# rk8-05.net
KiCad netlist of a schematic drawn in EAGLE
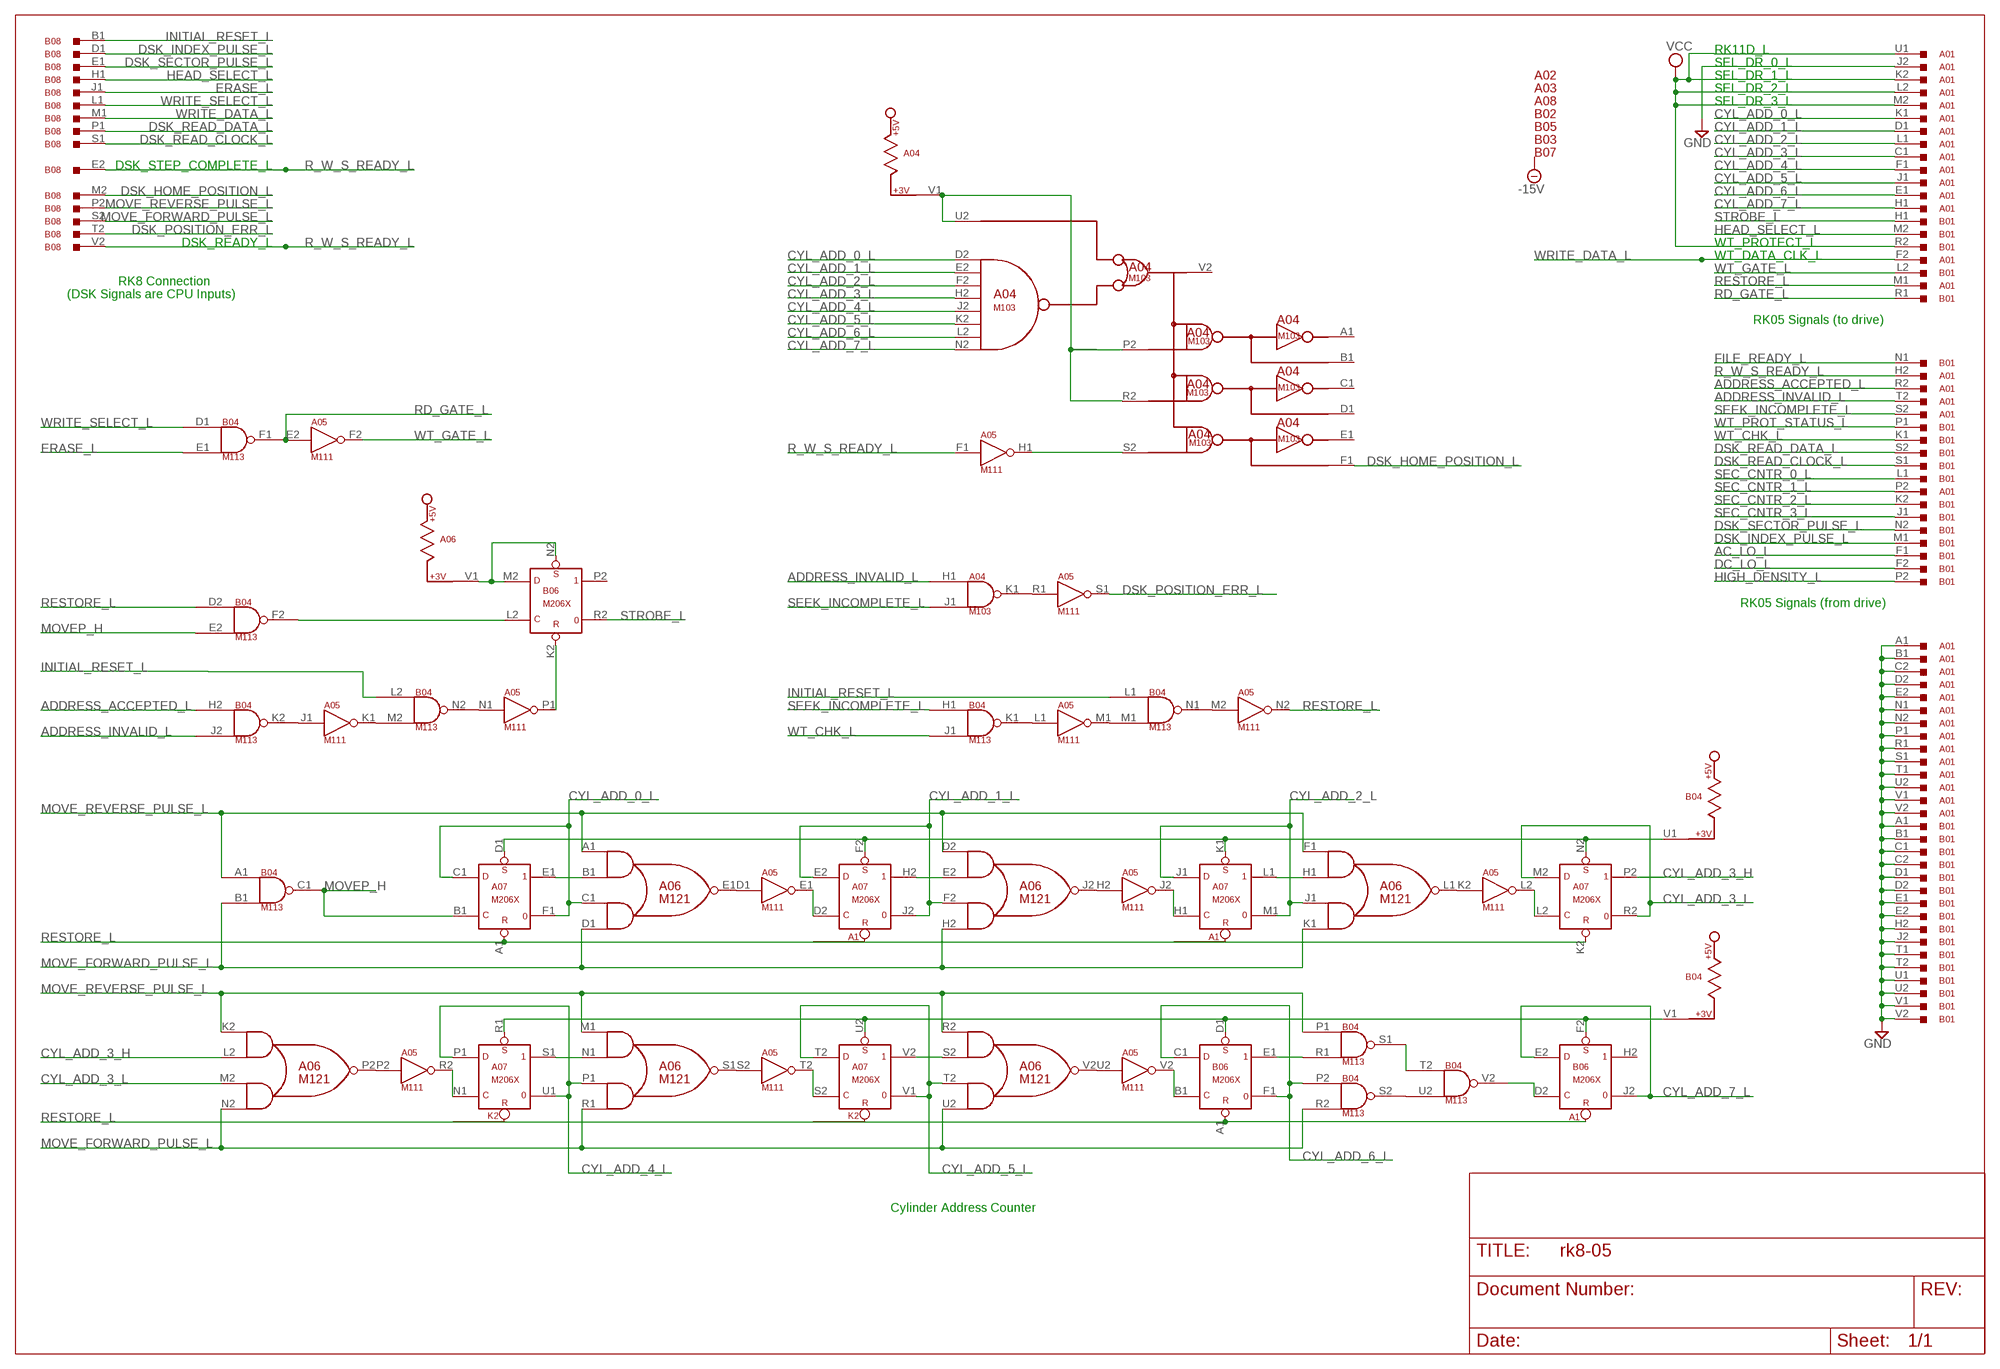
[diagram p0: schematic, sheet 1]

(export (version "E")
  (design (tool "Eeschema 10.0.6"))
  (components
    (comp (ref "A01")
      (value "M916")
      (footprint "eagle-import:H807")
      (libsource (lib "eagle-import") (part "M916"))
    )
    (comp (ref "A02")
      (value "EMPTY")
      (footprint "eagle-import:H807")
      (libsource (lib "eagle-import") (part "EMPTY"))
    )
    (comp (ref "A03")
      (value "EMPTY")
      (footprint "eagle-import:H807")
      (libsource (lib "eagle-import") (part "EMPTY"))
    )
    (comp (ref "A04")
      (value "M103")
      (footprint "eagle-import:H807")
      (libsource (lib "eagle-import") (part "M103"))
    )
    (comp (ref "A05")
      (value "M111")
      (footprint "eagle-import:H807")
      (libsource (lib "eagle-import") (part "M111"))
    )
    (comp (ref "A06")
      (value "M121")
      (footprint "eagle-import:H807")
      (libsource (lib "eagle-import") (part "M121"))
    )
    (comp (ref "A07")
      (value "M206X")
      (footprint "eagle-import:H807")
      (libsource (lib "eagle-import") (part "M206X"))
    )
    (comp (ref "A08")
      (value "EMPTY")
      (footprint "eagle-import:H807")
      (libsource (lib "eagle-import") (part "EMPTY"))
    )
    (comp (ref "B01")
      (value "M916")
      (footprint "eagle-import:H807")
      (libsource (lib "eagle-import") (part "M916"))
    )
    (comp (ref "B02")
      (value "EMPTY")
      (footprint "eagle-import:H807")
      (libsource (lib "eagle-import") (part "EMPTY"))
    )
    (comp (ref "B03")
      (value "EMPTY")
      (footprint "eagle-import:H807")
      (libsource (lib "eagle-import") (part "EMPTY"))
    )
    (comp (ref "B04")
      (value "M113")
      (footprint "eagle-import:H807")
      (libsource (lib "eagle-import") (part "M113"))
    )
    (comp (ref "B05")
      (value "EMPTY")
      (footprint "eagle-import:H807")
      (libsource (lib "eagle-import") (part "EMPTY"))
    )
    (comp (ref "B06")
      (value "M206X")
      (footprint "eagle-import:H807")
      (libsource (lib "eagle-import") (part "M206X"))
    )
    (comp (ref "B07")
      (value "EMPTY")
      (footprint "eagle-import:H807")
      (libsource (lib "eagle-import") (part "EMPTY"))
    )
    (comp (ref "B08")
      (value "M903")
      (footprint "eagle-import:H807")
      (libsource (lib "eagle-import") (part "M903"))
    )
  )
  (nets
    (net (code "2") (name "/AC_LO_L") (class "Default")
      (node (ref "B01") (pin "F1") (pinfunction "P$2_F1") (pintype "bidirectional"))
    )
    (net (code "3") (name "/ADDRESS_ACCEPTED_L") (class "Default")
      (node (ref "A01") (pin "R2") (pinfunction "P$2_R2") (pintype "bidirectional"))
      (node (ref "B04") (pin "H2") (pinfunction "IN1_H2") (pintype "input"))
    )
    (net (code "4") (name "/ADDRESS_INVALID_L") (class "Default")
      (node (ref "A01") (pin "T2") (pinfunction "P$2_T2") (pintype "bidirectional"))
      (node (ref "A04") (pin "H1") (pinfunction "IN1_H1") (pintype "input"))
      (node (ref "B04") (pin "J2") (pinfunction "IN2_J2") (pintype "input"))
    )
    (net (code "5") (name "/CYL_ADD_0_L") (class "Default")
      (node (ref "A01") (pin "K1") (pinfunction "P$2_K1") (pintype "bidirectional"))
      (node (ref "A04") (pin "D2") (pinfunction "D2_D2") (pintype "input"))
      (node (ref "A06") (pin "C1") (pinfunction "IN2A_C1") (pintype "input"))
      (node (ref "A07") (pin "C1") (pinfunction "D_C1") (pintype "input"))
      (node (ref "A07") (pin "F1") (pinfunction "0_F1") (pintype "output"))
    )
    (net (code "6") (name "/CYL_ADD_1_L") (class "Default")
      (node (ref "A01") (pin "D1") (pinfunction "P$2_D1") (pintype "bidirectional"))
      (node (ref "A04") (pin "E2") (pinfunction "E2_E2") (pintype "input"))
      (node (ref "A06") (pin "F2") (pinfunction "IN2A_F2") (pintype "input"))
      (node (ref "A07") (pin "E2") (pinfunction "D_E2") (pintype "input"))
      (node (ref "A07") (pin "J2") (pinfunction "0_J2") (pintype "output"))
    )
    (net (code "7") (name "/CYL_ADD_2_L") (class "Default")
      (node (ref "A01") (pin "L1") (pinfunction "P$2_L1") (pintype "bidirectional"))
      (node (ref "A04") (pin "F2") (pinfunction "F2_F2") (pintype "input"))
      (node (ref "A06") (pin "J1") (pinfunction "IN2A_J1") (pintype "input"))
      (node (ref "A07") (pin "J1") (pinfunction "D_J1") (pintype "input"))
      (node (ref "A07") (pin "M1") (pinfunction "0_M1") (pintype "output"))
    )
    (net (code "8") (name "/CYL_ADD_3_H") (class "Default")
      (node (ref "A06") (pin "L2") (pinfunction "IN1B_L2") (pintype "input"))
      (node (ref "A07") (pin "P2") (pinfunction "1_P2") (pintype "output"))
    )
    (net (code "9") (name "/CYL_ADD_3_L") (class "Default")
      (node (ref "A01") (pin "C1") (pinfunction "P$2_C1") (pintype "bidirectional"))
      (node (ref "A04") (pin "H2") (pinfunction "H2_H2") (pintype "input"))
      (node (ref "A06") (pin "M2") (pinfunction "IN2A_M2") (pintype "input"))
      (node (ref "A07") (pin "M2") (pinfunction "D_M2") (pintype "input"))
      (node (ref "A07") (pin "R2") (pinfunction "0_R2") (pintype "output"))
    )
    (net (code "10") (name "/CYL_ADD_4_L") (class "Default")
      (node (ref "A01") (pin "F1") (pinfunction "P$2_F1") (pintype "bidirectional"))
      (node (ref "A04") (pin "J2") (pinfunction "J2_J2") (pintype "input"))
      (node (ref "A06") (pin "P1") (pinfunction "IN2A_P1") (pintype "input"))
      (node (ref "A07") (pin "P1") (pinfunction "D_P1") (pintype "input"))
      (node (ref "A07") (pin "U1") (pinfunction "0_U1") (pintype "output"))
    )
    (net (code "11") (name "/CYL_ADD_5_L") (class "Default")
      (node (ref "A01") (pin "J1") (pinfunction "P$2_J1") (pintype "bidirectional"))
      (node (ref "A04") (pin "K2") (pinfunction "K2_K2") (pintype "input"))
      (node (ref "A06") (pin "T2") (pinfunction "IN2A_T2") (pintype "input"))
      (node (ref "A07") (pin "T2") (pinfunction "D_T2") (pintype "input"))
      (node (ref "A07") (pin "V1") (pinfunction "0_V1") (pintype "output"))
    )
    (net (code "12") (name "/CYL_ADD_6_L") (class "Default")
      (node (ref "A01") (pin "E1") (pinfunction "P$2_E1") (pintype "bidirectional"))
      (node (ref "A04") (pin "L2") (pinfunction "L2_L2") (pintype "input"))
      (node (ref "B04") (pin "P2") (pinfunction "IN1_P2") (pintype "input"))
      (node (ref "B06") (pin "C1") (pinfunction "D_C1") (pintype "input"))
      (node (ref "B06") (pin "F1") (pinfunction "0_F1") (pintype "output"))
    )
    (net (code "13") (name "/CYL_ADD_7_L") (class "Default")
      (node (ref "A01") (pin "H1") (pinfunction "P$2_H1") (pintype "bidirectional"))
      (node (ref "A04") (pin "N2") (pinfunction "N2_N2") (pintype "input"))
      (node (ref "B06") (pin "E2") (pinfunction "D_E2") (pintype "input"))
      (node (ref "B06") (pin "J2") (pinfunction "0_J2") (pintype "output"))
    )
    (net (code "14") (name "/DC_LO_L") (class "Default")
      (node (ref "B01") (pin "F2") (pinfunction "P$2_F2") (pintype "bidirectional"))
    )
    (net (code "15") (name "/DSK_HOME_POSITION_L") (class "Default")
      (node (ref "A04") (pin "F1") (pinfunction "F1_F1") (pintype "output"))
      (node (ref "B08") (pin "M2") (pinfunction "P$2_M2") (pintype "bidirectional"))
    )
    (net (code "16") (name "/DSK_INDEX_PULSE_L") (class "Default")
      (node (ref "B01") (pin "M1") (pinfunction "P$2_M1") (pintype "bidirectional"))
      (node (ref "B08") (pin "D1") (pinfunction "P$2_D1") (pintype "bidirectional"))
    )
    (net (code "17") (name "/DSK_POSITION_ERR_L") (class "Default")
      (node (ref "A05") (pin "S1") (pinfunction "OUT_S1") (pintype "output"))
      (node (ref "B08") (pin "T2") (pinfunction "P$2_T2") (pintype "bidirectional"))
    )
    (net (code "18") (name "/DSK_READ_CLOCK_L") (class "Default")
      (node (ref "B01") (pin "S1") (pinfunction "P$2_S1") (pintype "bidirectional"))
      (node (ref "B08") (pin "S1") (pinfunction "P$2_S1") (pintype "bidirectional"))
    )
    (net (code "19") (name "/DSK_READ_DATA_L") (class "Default")
      (node (ref "B01") (pin "S2") (pinfunction "P$2_S2") (pintype "bidirectional"))
      (node (ref "B08") (pin "P1") (pinfunction "P$2_P1") (pintype "bidirectional"))
    )
    (net (code "20") (name "/DSK_SECTOR_PULSE_L") (class "Default")
      (node (ref "B01") (pin "N2") (pinfunction "P$2_N2") (pintype "bidirectional"))
      (node (ref "B08") (pin "E1") (pinfunction "P$2_E1") (pintype "bidirectional"))
    )
    (net (code "21") (name "/ERASE_L") (class "Default")
      (node (ref "B04") (pin "E1") (pinfunction "IN2_E1") (pintype "input"))
      (node (ref "B08") (pin "J1") (pinfunction "P$2_J1") (pintype "bidirectional"))
    )
    (net (code "22") (name "/FILE_READY_L") (class "Default")
      (node (ref "B01") (pin "N1") (pinfunction "P$2_N1") (pintype "bidirectional"))
    )
    (net (code "23") (name "/HEAD_SELECT_L") (class "Default")
      (node (ref "B01") (pin "M2") (pinfunction "P$2_M2") (pintype "bidirectional"))
      (node (ref "B08") (pin "H1") (pinfunction "P$2_H1") (pintype "bidirectional"))
    )
    (net (code "24") (name "/HIGH_DENSITY_L") (class "Default")
      (node (ref "B01") (pin "P2") (pinfunction "P$2_P2") (pintype "bidirectional"))
    )
    (net (code "25") (name "/INITIAL_RESET_L") (class "Default")
      (node (ref "B04") (pin "L1") (pinfunction "IN1_L1") (pintype "input"))
      (node (ref "B04") (pin "L2") (pinfunction "IN1_L2") (pintype "input"))
      (node (ref "B08") (pin "B1") (pinfunction "P$2_B1") (pintype "bidirectional"))
    )
    (net (code "26") (name "/MOVEP_H") (class "Default")
      (node (ref "A07") (pin "B1") (pinfunction "C_B1") (pintype "input"))
      (node (ref "B04") (pin "C1") (pinfunction "OUT_C1") (pintype "output"))
      (node (ref "B04") (pin "E2") (pinfunction "IN2_E2") (pintype "input"))
    )
    (net (code "27") (name "/MOVE_FORWARD_PULSE_L") (class "Default")
      (node (ref "A06") (pin "D1") (pinfunction "IN2B_D1") (pintype "input"))
      (node (ref "A06") (pin "H2") (pinfunction "IN2B_H2") (pintype "input"))
      (node (ref "A06") (pin "K1") (pinfunction "IN2B_K1") (pintype "input"))
      (node (ref "A06") (pin "N2") (pinfunction "IN2B_N2") (pintype "input"))
      (node (ref "A06") (pin "R1") (pinfunction "IN2B_R1") (pintype "input"))
      (node (ref "A06") (pin "U2") (pinfunction "IN2B_U2") (pintype "input"))
      (node (ref "B04") (pin "B1") (pinfunction "IN2_B1") (pintype "input"))
      (node (ref "B04") (pin "R2") (pinfunction "IN2_R2") (pintype "input"))
      (node (ref "B08") (pin "S2") (pinfunction "P$2_S2") (pintype "bidirectional"))
    )
    (net (code "28") (name "/MOVE_REVERSE_PULSE_L") (class "Default")
      (node (ref "A06") (pin "A1") (pinfunction "IN1A_A1") (pintype "input"))
      (node (ref "A06") (pin "D2") (pinfunction "IN1A_D2") (pintype "input"))
      (node (ref "A06") (pin "F1") (pinfunction "IN1A_F1") (pintype "input"))
      (node (ref "A06") (pin "K2") (pinfunction "IN1A_K2") (pintype "input"))
      (node (ref "A06") (pin "M1") (pinfunction "IN1A_M1") (pintype "input"))
      (node (ref "A06") (pin "R2") (pinfunction "IN1A_R2") (pintype "input"))
      (node (ref "B04") (pin "A1") (pinfunction "IN1_A1") (pintype "input"))
      (node (ref "B04") (pin "P1") (pinfunction "IN1_P1") (pintype "input"))
      (node (ref "B08") (pin "P2") (pinfunction "P$2_P2") (pintype "bidirectional"))
    )
    (net (code "29") (name "/RD_GATE_L") (class "Default")
      (node (ref "A05") (pin "E2") (pinfunction "IN_E2") (pintype "input"))
      (node (ref "B01") (pin "R1") (pinfunction "P$2_R1") (pintype "bidirectional"))
      (node (ref "B04") (pin "F1") (pinfunction "OUT_F1") (pintype "output"))
    )
    (net (code "30") (name "/RESTORE_L") (class "Default")
      (node (ref "A01") (pin "M1") (pinfunction "P$2_M1") (pintype "bidirectional"))
      (node (ref "A05") (pin "N2") (pinfunction "OUT_N2") (pintype "output"))
      (node (ref "A07") (pin "A1") (pinfunction "R_A1") (pintype "input"))
      (node (ref "A07") (pin "K2") (pinfunction "R_K2") (pintype "input"))
      (node (ref "B04") (pin "D2") (pinfunction "IN1_D2") (pintype "input"))
      (node (ref "B06") (pin "A1") (pinfunction "R_A1") (pintype "input"))
    )
    (net (code "31") (name "/R_W_S_READY_L") (class "Default")
      (node (ref "A01") (pin "H2") (pinfunction "P$2_H2") (pintype "bidirectional"))
      (node (ref "A05") (pin "F1") (pinfunction "IN_F1") (pintype "input"))
      (node (ref "B08") (pin "E2") (pinfunction "P$2_E2") (pintype "bidirectional"))
      (node (ref "B08") (pin "V2") (pinfunction "P$2_V2") (pintype "bidirectional"))
    )
    (net (code "32") (name "/SEC_CNTR_0_L") (class "Default")
      (node (ref "B01") (pin "L1") (pinfunction "P$2_L1") (pintype "bidirectional"))
    )
    (net (code "33") (name "/SEC_CNTR_1_L") (class "Default")
      (node (ref "A01") (pin "P2") (pinfunction "P$2_P2") (pintype "bidirectional"))
    )
    (net (code "34") (name "/SEC_CNTR_2_L") (class "Default")
      (node (ref "B01") (pin "K2") (pinfunction "P$2_K2") (pintype "bidirectional"))
    )
    (net (code "35") (name "/SEC_CNTR_3_L") (class "Default")
      (node (ref "B01") (pin "J1") (pinfunction "P$2_J1") (pintype "bidirectional"))
    )
    (net (code "36") (name "/SEEK_INCOMPLETE_L") (class "Default")
      (node (ref "A01") (pin "S2") (pinfunction "P$2_S2") (pintype "bidirectional"))
      (node (ref "A04") (pin "J1") (pinfunction "IN2_J1") (pintype "input"))
      (node (ref "B04") (pin "H1") (pinfunction "IN1_H1") (pintype "input"))
    )
    (net (code "37") (name "/STROBE_L") (class "Default")
      (node (ref "B01") (pin "H1") (pinfunction "P$2_H1") (pintype "bidirectional"))
      (node (ref "B06") (pin "R2") (pinfunction "0_R2") (pintype "output"))
    )
    (net (code "38") (name "/WRITE_DATA_L") (class "Default")
      (node (ref "A01") (pin "F2") (pinfunction "P$2_F2") (pintype "bidirectional"))
      (node (ref "B08") (pin "M1") (pinfunction "P$2_M1") (pintype "bidirectional"))
    )
    (net (code "39") (name "/WRITE_SELECT_L") (class "Default")
      (node (ref "B04") (pin "D1") (pinfunction "IN1_D1") (pintype "input"))
      (node (ref "B08") (pin "L1") (pinfunction "P$2_L1") (pintype "bidirectional"))
    )
    (net (code "40") (name "/WT_CHK_L") (class "Default")
      (node (ref "B01") (pin "K1") (pinfunction "P$2_K1") (pintype "bidirectional"))
      (node (ref "B04") (pin "J1") (pinfunction "IN2_J1") (pintype "input"))
    )
    (net (code "41") (name "/WT_GATE_L") (class "Default")
      (node (ref "A05") (pin "F2") (pinfunction "OUT_F2") (pintype "output"))
      (node (ref "B01") (pin "L2") (pinfunction "P$2_L2") (pintype "bidirectional"))
    )
    (net (code "42") (name "/WT_PROT_STATUS_L") (class "Default")
      (node (ref "B01") (pin "P1") (pinfunction "P$2_P1") (pintype "bidirectional"))
    )
    (net (code "43") (name "GND") (class "Default")
      (node (ref "A01") (pin "A1") (pinfunction "P$2_A1") (pintype "bidirectional"))
      (node (ref "A01") (pin "B1") (pinfunction "P$2_B1") (pintype "bidirectional"))
      (node (ref "A01") (pin "C2") (pinfunction "P$2_C2") (pintype "bidirectional"))
      (node (ref "A01") (pin "D2") (pinfunction "P$2_D2") (pintype "bidirectional"))
      (node (ref "A01") (pin "E2") (pinfunction "P$2_E2") (pintype "bidirectional"))
      (node (ref "A01") (pin "J2") (pinfunction "P$2_J2") (pintype "bidirectional"))
      (node (ref "A01") (pin "N1") (pinfunction "P$2_N1") (pintype "bidirectional"))
      (node (ref "A01") (pin "N2") (pinfunction "P$2_N2") (pintype "bidirectional"))
      (node (ref "A01") (pin "P1") (pinfunction "P$2_P1") (pintype "bidirectional"))
      (node (ref "A01") (pin "R1") (pinfunction "P$2_R1") (pintype "bidirectional"))
      (node (ref "A01") (pin "S1") (pinfunction "P$2_S1") (pintype "bidirectional"))
      (node (ref "A01") (pin "T1") (pinfunction "P$2_T1") (pintype "bidirectional"))
      (node (ref "A01") (pin "U2") (pinfunction "P$2_U2") (pintype "bidirectional"))
      (node (ref "A01") (pin "V1") (pinfunction "P$2_V1") (pintype "bidirectional"))
      (node (ref "A01") (pin "V2") (pinfunction "P$2_V2") (pintype "bidirectional"))
      (node (ref "B01") (pin "A1") (pinfunction "P$2_A1") (pintype "bidirectional"))
      (node (ref "B01") (pin "B1") (pinfunction "P$2_B1") (pintype "bidirectional"))
      (node (ref "B01") (pin "C1") (pinfunction "P$2_C1") (pintype "bidirectional"))
      (node (ref "B01") (pin "C2") (pinfunction "P$2_C2") (pintype "bidirectional"))
      (node (ref "B01") (pin "D1") (pinfunction "P$2_D1") (pintype "bidirectional"))
      (node (ref "B01") (pin "D2") (pinfunction "P$2_D2") (pintype "bidirectional"))
      (node (ref "B01") (pin "E1") (pinfunction "P$2_E1") (pintype "bidirectional"))
      (node (ref "B01") (pin "E2") (pinfunction "P$2_E2") (pintype "bidirectional"))
      (node (ref "B01") (pin "H2") (pinfunction "P$2_H2") (pintype "bidirectional"))
      (node (ref "B01") (pin "J2") (pinfunction "P$2_J2") (pintype "bidirectional"))
      (node (ref "B01") (pin "T1") (pinfunction "P$2_T1") (pintype "bidirectional"))
      (node (ref "B01") (pin "T2") (pinfunction "P$2_T2") (pintype "bidirectional"))
      (node (ref "B01") (pin "U1") (pinfunction "P$2_U1") (pintype "bidirectional"))
      (node (ref "B01") (pin "U2") (pinfunction "P$2_U2") (pintype "bidirectional"))
      (node (ref "B01") (pin "V1") (pinfunction "P$2_V1") (pintype "bidirectional"))
      (node (ref "B01") (pin "V2") (pinfunction "P$2_V2") (pintype "bidirectional"))
    )
    (net (code "44") (name "Net-(A04C-OUT)") (class "Default")
      (node (ref "A04") (pin "K1") (pinfunction "OUT_K1") (pintype "output"))
      (node (ref "A05") (pin "R1") (pinfunction "IN_R1") (pintype "input"))
    )
    (net (code "45") (name "Net-(A04E-P$1)") (class "Default")
      (node (ref "A04") (pin "P2") (pinfunction "P2_P2") (pintype "input"))
      (node (ref "A04") (pin "R2") (pinfunction "R2_R2") (pintype "input"))
      (node (ref "A04") (pin "U2") (pinfunction "U2_U2") (pintype "input"))
      (node (ref "A04") (pin "V1") (pinfunction "P$1_V1") (pintype "passive"))
    )
    (net (code "46") (name "Net-(A05C-IN)") (class "Default")
      (node (ref "A05") (pin "D1") (pinfunction "IN_D1") (pintype "input"))
      (node (ref "A06") (pin "E1") (pinfunction "OUT_E1") (pintype "output"))
    )
    (net (code "47") (name "Net-(A05C-OUT)") (class "Default")
      (node (ref "A05") (pin "E1") (pinfunction "OUT_E1") (pintype "output"))
      (node (ref "A07") (pin "D2") (pinfunction "C_D2") (pintype "input"))
    )
    (net (code "48") (name "Net-(A05G-OUT)") (class "Default")
      (node (ref "A04") (pin "S2") (pinfunction "S2_S2") (pintype "input"))
      (node (ref "A05") (pin "H1") (pinfunction "OUT_H1") (pintype "output"))
    )
    (net (code "49") (name "Net-(A05H-IN)") (class "Default")
      (node (ref "A05") (pin "H2") (pinfunction "IN_H2") (pintype "input"))
      (node (ref "A06") (pin "J2") (pinfunction "OUT_J2") (pintype "output"))
    )
    (net (code "50") (name "Net-(A05H-OUT)") (class "Default")
      (node (ref "A05") (pin "J2") (pinfunction "OUT_J2") (pintype "output"))
      (node (ref "A07") (pin "H1") (pinfunction "C_H1") (pintype "input"))
    )
    (net (code "51") (name "Net-(A05I-IN)") (class "Default")
      (node (ref "A05") (pin "J1") (pinfunction "IN_J1") (pintype "input"))
      (node (ref "B04") (pin "K2") (pinfunction "OUT_K2") (pintype "output"))
    )
    (net (code "52") (name "Net-(A05I-OUT)") (class "Default")
      (node (ref "A05") (pin "K1") (pinfunction "OUT_K1") (pintype "output"))
      (node (ref "B04") (pin "M2") (pinfunction "IN2_M2") (pintype "input"))
    )
    (net (code "53") (name "Net-(A05J-IN)") (class "Default")
      (node (ref "A05") (pin "K2") (pinfunction "IN_K2") (pintype "input"))
      (node (ref "A06") (pin "L1") (pinfunction "OUT_L1") (pintype "output"))
    )
    (net (code "54") (name "Net-(A05J-OUT)") (class "Default")
      (node (ref "A05") (pin "L2") (pinfunction "OUT_L2") (pintype "output"))
      (node (ref "A07") (pin "L2") (pinfunction "C_L2") (pintype "input"))
    )
    (net (code "55") (name "Net-(A05K-IN)") (class "Default")
      (node (ref "A05") (pin "L1") (pinfunction "IN_L1") (pintype "input"))
      (node (ref "B04") (pin "K1") (pinfunction "OUT_K1") (pintype "output"))
    )
    (net (code "56") (name "Net-(A05K-OUT)") (class "Default")
      (node (ref "A05") (pin "M1") (pinfunction "OUT_M1") (pintype "output"))
      (node (ref "B04") (pin "M1") (pinfunction "IN2_M1") (pintype "input"))
    )
    (net (code "57") (name "Net-(A05L-IN)") (class "Default")
      (node (ref "A05") (pin "M2") (pinfunction "IN_M2") (pintype "input"))
      (node (ref "B04") (pin "N1") (pinfunction "OUT_N1") (pintype "output"))
    )
    (net (code "58") (name "Net-(A05M-IN)") (class "Default")
      (node (ref "A05") (pin "N1") (pinfunction "IN_N1") (pintype "input"))
      (node (ref "B04") (pin "N2") (pinfunction "OUT_N2") (pintype "output"))
    )
    (net (code "59") (name "Net-(A05M-OUT)") (class "Default")
      (node (ref "A05") (pin "P1") (pinfunction "OUT_P1") (pintype "output"))
      (node (ref "B06") (pin "K2") (pinfunction "R_K2") (pintype "input"))
    )
    (net (code "60") (name "Net-(A05N-IN)") (class "Default")
      (node (ref "A05") (pin "P2") (pinfunction "IN_P2") (pintype "input"))
      (node (ref "A06") (pin "P2") (pinfunction "OUT_P2") (pintype "output"))
    )
    (net (code "61") (name "Net-(A05N-OUT)") (class "Default")
      (node (ref "A05") (pin "R2") (pinfunction "OUT_R2") (pintype "output"))
      (node (ref "A07") (pin "N1") (pinfunction "C_N1") (pintype "input"))
    )
    (net (code "62") (name "Net-(A05P-IN)") (class "Default")
      (node (ref "A05") (pin "S2") (pinfunction "IN_S2") (pintype "input"))
      (node (ref "A06") (pin "S1") (pinfunction "OUT_S1") (pintype "output"))
    )
    (net (code "63") (name "Net-(A05P-OUT)") (class "Default")
      (node (ref "A05") (pin "T2") (pinfunction "OUT_T2") (pintype "output"))
      (node (ref "A07") (pin "S2") (pinfunction "C_S2") (pintype "input"))
    )
    (net (code "64") (name "Net-(A05R-IN)") (class "Default")
      (node (ref "A05") (pin "U2") (pinfunction "IN_U2") (pintype "input"))
      (node (ref "A06") (pin "V2") (pinfunction "OUT_V2") (pintype "output"))
    )
    (net (code "65") (name "Net-(A05R-OUT)") (class "Default")
      (node (ref "A05") (pin "V2") (pinfunction "OUT_V2") (pintype "output"))
      (node (ref "B06") (pin "B1") (pinfunction "C_B1") (pintype "input"))
    )
    (net (code "66") (name "Net-(A06A-IN1B)") (class "Default")
      (node (ref "A06") (pin "B1") (pinfunction "IN1B_B1") (pintype "input"))
      (node (ref "A07") (pin "E1") (pinfunction "1_E1") (pintype "output"))
    )
    (net (code "67") (name "Net-(A06D-IN1B)") (class "Default")
      (node (ref "A06") (pin "E2") (pinfunction "IN1B_E2") (pintype "input"))
      (node (ref "A07") (pin "H2") (pinfunction "1_H2") (pintype "output"))
    )
    (net (code "68") (name "Net-(A06E-IN1B)") (class "Default")
      (node (ref "A06") (pin "H1") (pinfunction "IN1B_H1") (pintype "input"))
      (node (ref "A07") (pin "L1") (pinfunction "1_L1") (pintype "output"))
    )
    (net (code "69") (name "Net-(A06G-IN1B)") (class "Default")
      (node (ref "A06") (pin "N1") (pinfunction "IN1B_N1") (pintype "input"))
      (node (ref "A07") (pin "S1") (pinfunction "1_S1") (pintype "output"))
    )
    (net (code "70") (name "Net-(A06I-P$1)") (class "Default")
      (node (ref "A06") (pin "V1") (pinfunction "P$1_V1") (pintype "passive"))
      (node (ref "B06") (pin "M2") (pinfunction "D_M2") (pintype "input"))
      (node (ref "B06") (pin "N2") (pinfunction "S_N2") (pintype "input"))
    )
    (net (code "71") (name "Net-(A06J-IN1B)") (class "Default")
      (node (ref "A06") (pin "S2") (pinfunction "IN1B_S2") (pintype "input"))
      (node (ref "A07") (pin "V2") (pinfunction "1_V2") (pintype "output"))
    )
    (net (code "72") (name "Net-(A07A-S)") (class "Default")
      (node (ref "A07") (pin "D1") (pinfunction "S_D1") (pintype "input"))
      (node (ref "A07") (pin "F2") (pinfunction "S_F2") (pintype "input"))
      (node (ref "A07") (pin "K1") (pinfunction "S_K1") (pintype "input"))
      (node (ref "A07") (pin "N2") (pinfunction "S_N2") (pintype "input"))
      (node (ref "B04") (pin "U1") (pinfunction "P$1_U1") (pintype "passive"))
    )
    (net (code "73") (name "Net-(A07G-S)") (class "Default")
      (node (ref "A07") (pin "R1") (pinfunction "S_R1") (pintype "input"))
      (node (ref "A07") (pin "U2") (pinfunction "S_U2") (pintype "input"))
      (node (ref "B04") (pin "V1") (pinfunction "P$1_V1") (pintype "passive"))
      (node (ref "B06") (pin "D1") (pinfunction "S_D1") (pintype "input"))
      (node (ref "B06") (pin "F2") (pinfunction "S_F2") (pintype "input"))
    )
    (net (code "74") (name "Net-(B04C-OUT)") (class "Default")
      (node (ref "B04") (pin "F2") (pinfunction "OUT_F2") (pintype "output"))
      (node (ref "B06") (pin "L2") (pinfunction "C_L2") (pintype "input"))
    )
    (net (code "75") (name "Net-(B04J-IN2)") (class "Default")
      (node (ref "B04") (pin "R1") (pinfunction "IN2_R1") (pintype "input"))
      (node (ref "B06") (pin "E1") (pinfunction "1_E1") (pintype "output"))
    )
    (net (code "76") (name "Net-(B04J-OUT)") (class "Default")
      (node (ref "B04") (pin "S1") (pinfunction "OUT_S1") (pintype "output"))
      (node (ref "B04") (pin "T2") (pinfunction "IN1_T2") (pintype "input"))
    )
    (net (code "77") (name "Net-(B04K-OUT)") (class "Default")
      (node (ref "B04") (pin "S2") (pinfunction "OUT_S2") (pintype "output"))
      (node (ref "B04") (pin "U2") (pinfunction "IN2_U2") (pintype "input"))
    )
    (net (code "78") (name "Net-(B04N-OUT)") (class "Default")
      (node (ref "B04") (pin "V2") (pinfunction "OUT_V2") (pintype "output"))
      (node (ref "B06") (pin "D2") (pinfunction "C_D2") (pintype "input"))
    )
    (net (code "79") (name "VCC") (class "Default")
      (node (ref "A01") (pin "K2") (pinfunction "P$2_K2") (pintype "bidirectional"))
      (node (ref "A01") (pin "L2") (pinfunction "P$2_L2") (pintype "bidirectional"))
      (node (ref "A01") (pin "M2") (pinfunction "P$2_M2") (pintype "bidirectional"))
      (node (ref "A01") (pin "U1") (pinfunction "P$2_U1") (pintype "bidirectional"))
      (node (ref "B01") (pin "R2") (pinfunction "P$2_R2") (pintype "bidirectional"))
    )
    (net (code "80") (name "unconnected-(A04-PadA1)") (class "Default")
      (node (ref "A04") (pin "A1") (pinfunction "A1_A1") (pintype "output"))
    )
    (net (code "81") (name "unconnected-(A04-PadB1)") (class "Default")
      (node (ref "A04") (pin "B1") (pinfunction "B1_B1") (pintype "output"))
    )
    (net (code "82") (name "unconnected-(A04-PadC1)") (class "Default")
      (node (ref "A04") (pin "C1") (pinfunction "C1_C1") (pintype "output"))
    )
    (net (code "83") (name "unconnected-(A04-PadD1)") (class "Default")
      (node (ref "A04") (pin "D1") (pinfunction "D1_D1") (pintype "output"))
    )
    (net (code "84") (name "unconnected-(A04-PadE1)") (class "Default")
      (node (ref "A04") (pin "E1") (pinfunction "E1_E1") (pintype "output"))
    )
    (net (code "85") (name "unconnected-(A04-PadV2)") (class "Default")
      (node (ref "A04") (pin "V2") (pinfunction "V2_V2") (pintype "output"))
    )
    (net (code "86") (name "unconnected-(B06D-1-PadH2)") (class "Default")
      (node (ref "B06") (pin "H2") (pinfunction "1_H2") (pintype "output"))
    )
    (net (code "87") (name "unconnected-(B06F-1-PadP2)") (class "Default")
      (node (ref "B06") (pin "P2") (pinfunction "1_P2") (pintype "output"))
    )
  )
)
